# 2s.net
KiCad netlist of a schematic drawn in Altium Designer
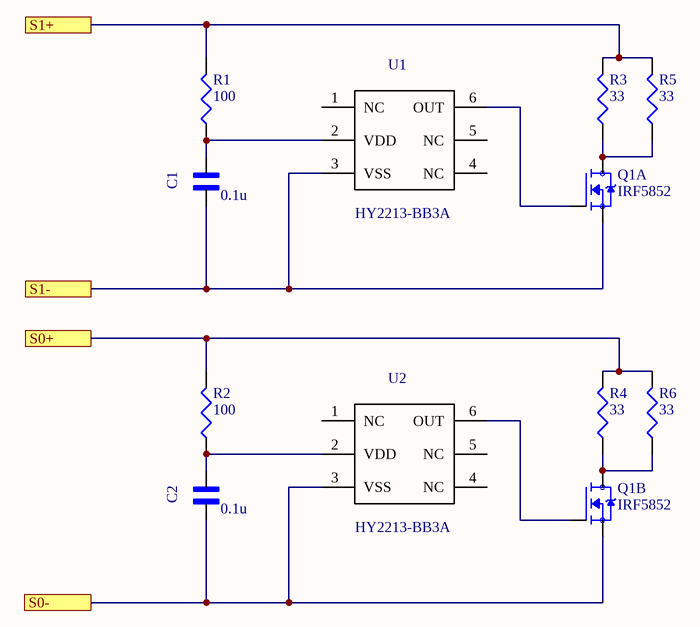
[diagram p0: 2s.SchDoc]

(export (version "E")
  (design (tool "Eeschema 10.0.6"))
  (components
    (comp (ref "C1")
      (value "0.1u")
      (footprint "*CAPC1608X90")
      (description "Cap Thin Film 0.1uf 50v 0603")
      (fields (field (name "MF") "AVX") (field (name "MP") "GX035C104MAT2-500 or CL10B104JB8NNNC"))
      (libsource (lib "lib") (part "GX035C104MAT2-500"))
    )
    (comp (ref "C2")
      (value "0.1u")
      (footprint "*CAPC1608X90")
      (description "Cap Thin Film 0.1uf 50v 0603")
      (fields (field (name "MF") "AVX") (field (name "MP") "GX035C104MAT2-500 or CL10B104JB8NNNC"))
      (libsource (lib "lib") (part "GX035C104MAT2-500"))
    )
    (comp (ref "Q1")
      (value "IRF5852")
      (footprint "SOT23-6")
      (description "Mosfet Array 2 N-Channel _Dual_ 20V 2.7A 960mW Surface Mount 6-TSOP")
      (fields (field (name "MF") "Infineon"))
      (libsource (lib "lib") (part "IRF5852"))
    )
    (comp (ref "R1")
      (value "100")
      (footprint "J1-0603")
      (description "Resistor")
      (fields (field (name "Comment") "Res3") (field (name "PUBLISHER") "Altium Limited"))
      (libsource (lib "Miscellaneous Devices") (part "Res3"))
    )
    (comp (ref "R2")
      (value "100")
      (footprint "J1-0603")
      (description "Resistor")
      (fields (field (name "Comment") "Res3") (field (name "PUBLISHER") "Altium Limited"))
      (libsource (lib "Miscellaneous Devices") (part "Res3"))
    )
    (comp (ref "R3")
      (value "33")
      (footprint "12Z-2010")
      (description "Resistor")
      (fields (field (name "Comment") "Res3") (field (name "PUBLISHER") "Altium Limited"))
      (libsource (lib "Miscellaneous Devices") (part "Res3"))
    )
    (comp (ref "R4")
      (value "33")
      (footprint "12Z-2010")
      (description "Resistor")
      (fields (field (name "Comment") "Res3") (field (name "PUBLISHER") "Altium Limited"))
      (libsource (lib "Miscellaneous Devices") (part "Res3"))
    )
    (comp (ref "R5")
      (value "33")
      (footprint "12Z-2010")
      (description "Resistor")
      (fields (field (name "Comment") "Res3") (field (name "PUBLISHER") "Altium Limited"))
      (libsource (lib "Miscellaneous Devices") (part "Res3"))
    )
    (comp (ref "R6")
      (value "33")
      (footprint "12Z-2010")
      (description "Resistor")
      (fields (field (name "Comment") "Res3") (field (name "PUBLISHER") "Altium Limited"))
      (libsource (lib "Miscellaneous Devices") (part "Res3"))
    )
    (comp (ref "U1")
      (value "HY2213-BB3A")
      (footprint "sot23-6")
      (fields (field (name "MF") "infineon") (field (name "MP") "IRS10752LTRPBF"))
      (libsource (lib "lib") (part "HY2213-BB3A"))
    )
    (comp (ref "U2")
      (value "HY2213-BB3A")
      (footprint "sot23-6")
      (fields (field (name "MF") "infineon") (field (name "MP") "IRS10752LTRPBF"))
      (libsource (lib "lib") (part "HY2213-BB3A"))
    )
  )
  (nets
    (net (code "1") (name "/S0+") (class "Default")
      (node (ref "R2") (pin "2") (pinfunction "2_2") (pintype "passive"))
      (node (ref "R4") (pin "2") (pinfunction "2_2") (pintype "passive"))
      (node (ref "R6") (pin "2") (pinfunction "2_2") (pintype "passive"))
    )
    (net (code "2") (name "/S0-") (class "Default")
      (node (ref "C2") (pin "2") (pinfunction "2_2") (pintype "passive"))
      (node (ref "Q1") (pin "4") (pinfunction "S_4") (pintype "passive"))
      (node (ref "U2") (pin "3") (pinfunction "VSS_3") (pintype "power_in"))
    )
    (net (code "3") (name "/S1+") (class "Default")
      (node (ref "R1") (pin "2") (pinfunction "2_2") (pintype "passive"))
      (node (ref "R3") (pin "2") (pinfunction "2_2") (pintype "passive"))
      (node (ref "R5") (pin "2") (pinfunction "2_2") (pintype "passive"))
    )
    (net (code "4") (name "/S1-") (class "Default")
      (node (ref "C1") (pin "2") (pinfunction "2_2") (pintype "passive"))
      (node (ref "Q1") (pin "5") (pinfunction "S_5") (pintype "passive"))
      (node (ref "U1") (pin "3") (pinfunction "VSS_3") (pintype "power_in"))
    )
    (net (code "5") (name "Net-(Q1A-D)") (class "Default")
      (node (ref "Q1") (pin "6") (pinfunction "D_6") (pintype "passive"))
      (node (ref "R3") (pin "1") (pinfunction "1_1") (pintype "passive"))
      (node (ref "R5") (pin "1") (pinfunction "1_1") (pintype "passive"))
    )
    (net (code "6") (name "Net-(Q1A-G)") (class "Default")
      (node (ref "Q1") (pin "1") (pinfunction "G_1") (pintype "passive"))
      (node (ref "U1") (pin "6") (pinfunction "OUT_6") (pintype "power_in"))
    )
    (net (code "7") (name "Net-(Q1B-D)") (class "Default")
      (node (ref "Q1") (pin "2") (pinfunction "D_2") (pintype "passive"))
      (node (ref "R4") (pin "1") (pinfunction "1_1") (pintype "passive"))
      (node (ref "R6") (pin "1") (pinfunction "1_1") (pintype "passive"))
    )
    (net (code "8") (name "Net-(Q1B-G)") (class "Default")
      (node (ref "Q1") (pin "3") (pinfunction "G_3") (pintype "passive"))
      (node (ref "U2") (pin "6") (pinfunction "OUT_6") (pintype "power_in"))
    )
    (net (code "9") (name "Net-(U1-VDD)") (class "Default")
      (node (ref "C1") (pin "1") (pinfunction "1_1") (pintype "passive"))
      (node (ref "R1") (pin "1") (pinfunction "1_1") (pintype "passive"))
      (node (ref "U1") (pin "2") (pinfunction "VDD_2") (pintype "passive"))
    )
    (net (code "10") (name "Net-(U2-VDD)") (class "Default")
      (node (ref "C2") (pin "1") (pinfunction "1_1") (pintype "passive"))
      (node (ref "R2") (pin "1") (pinfunction "1_1") (pintype "passive"))
      (node (ref "U2") (pin "2") (pinfunction "VDD_2") (pintype "passive"))
    )
    (net (code "11") (name "unconnected-(U1-NC-Pad1)") (class "Default")
      (node (ref "U1") (pin "1") (pinfunction "NC_1") (pintype "power_in"))
    )
    (net (code "12") (name "unconnected-(U1-NC-Pad4)") (class "Default")
      (node (ref "U1") (pin "4") (pinfunction "NC_4") (pintype "power_in"))
    )
    (net (code "13") (name "unconnected-(U1-NC-Pad5)") (class "Default")
      (node (ref "U1") (pin "5") (pinfunction "NC_5") (pintype "passive"))
    )
    (net (code "14") (name "unconnected-(U2-NC-Pad1)") (class "Default")
      (node (ref "U2") (pin "1") (pinfunction "NC_1") (pintype "power_in"))
    )
    (net (code "15") (name "unconnected-(U2-NC-Pad4)") (class "Default")
      (node (ref "U2") (pin "4") (pinfunction "NC_4") (pintype "power_in"))
    )
    (net (code "16") (name "unconnected-(U2-NC-Pad5)") (class "Default")
      (node (ref "U2") (pin "5") (pinfunction "NC_5") (pintype "passive"))
    )
  )
)
